# MP3_Shield.net
KiCad netlist of a schematic drawn in EAGLE
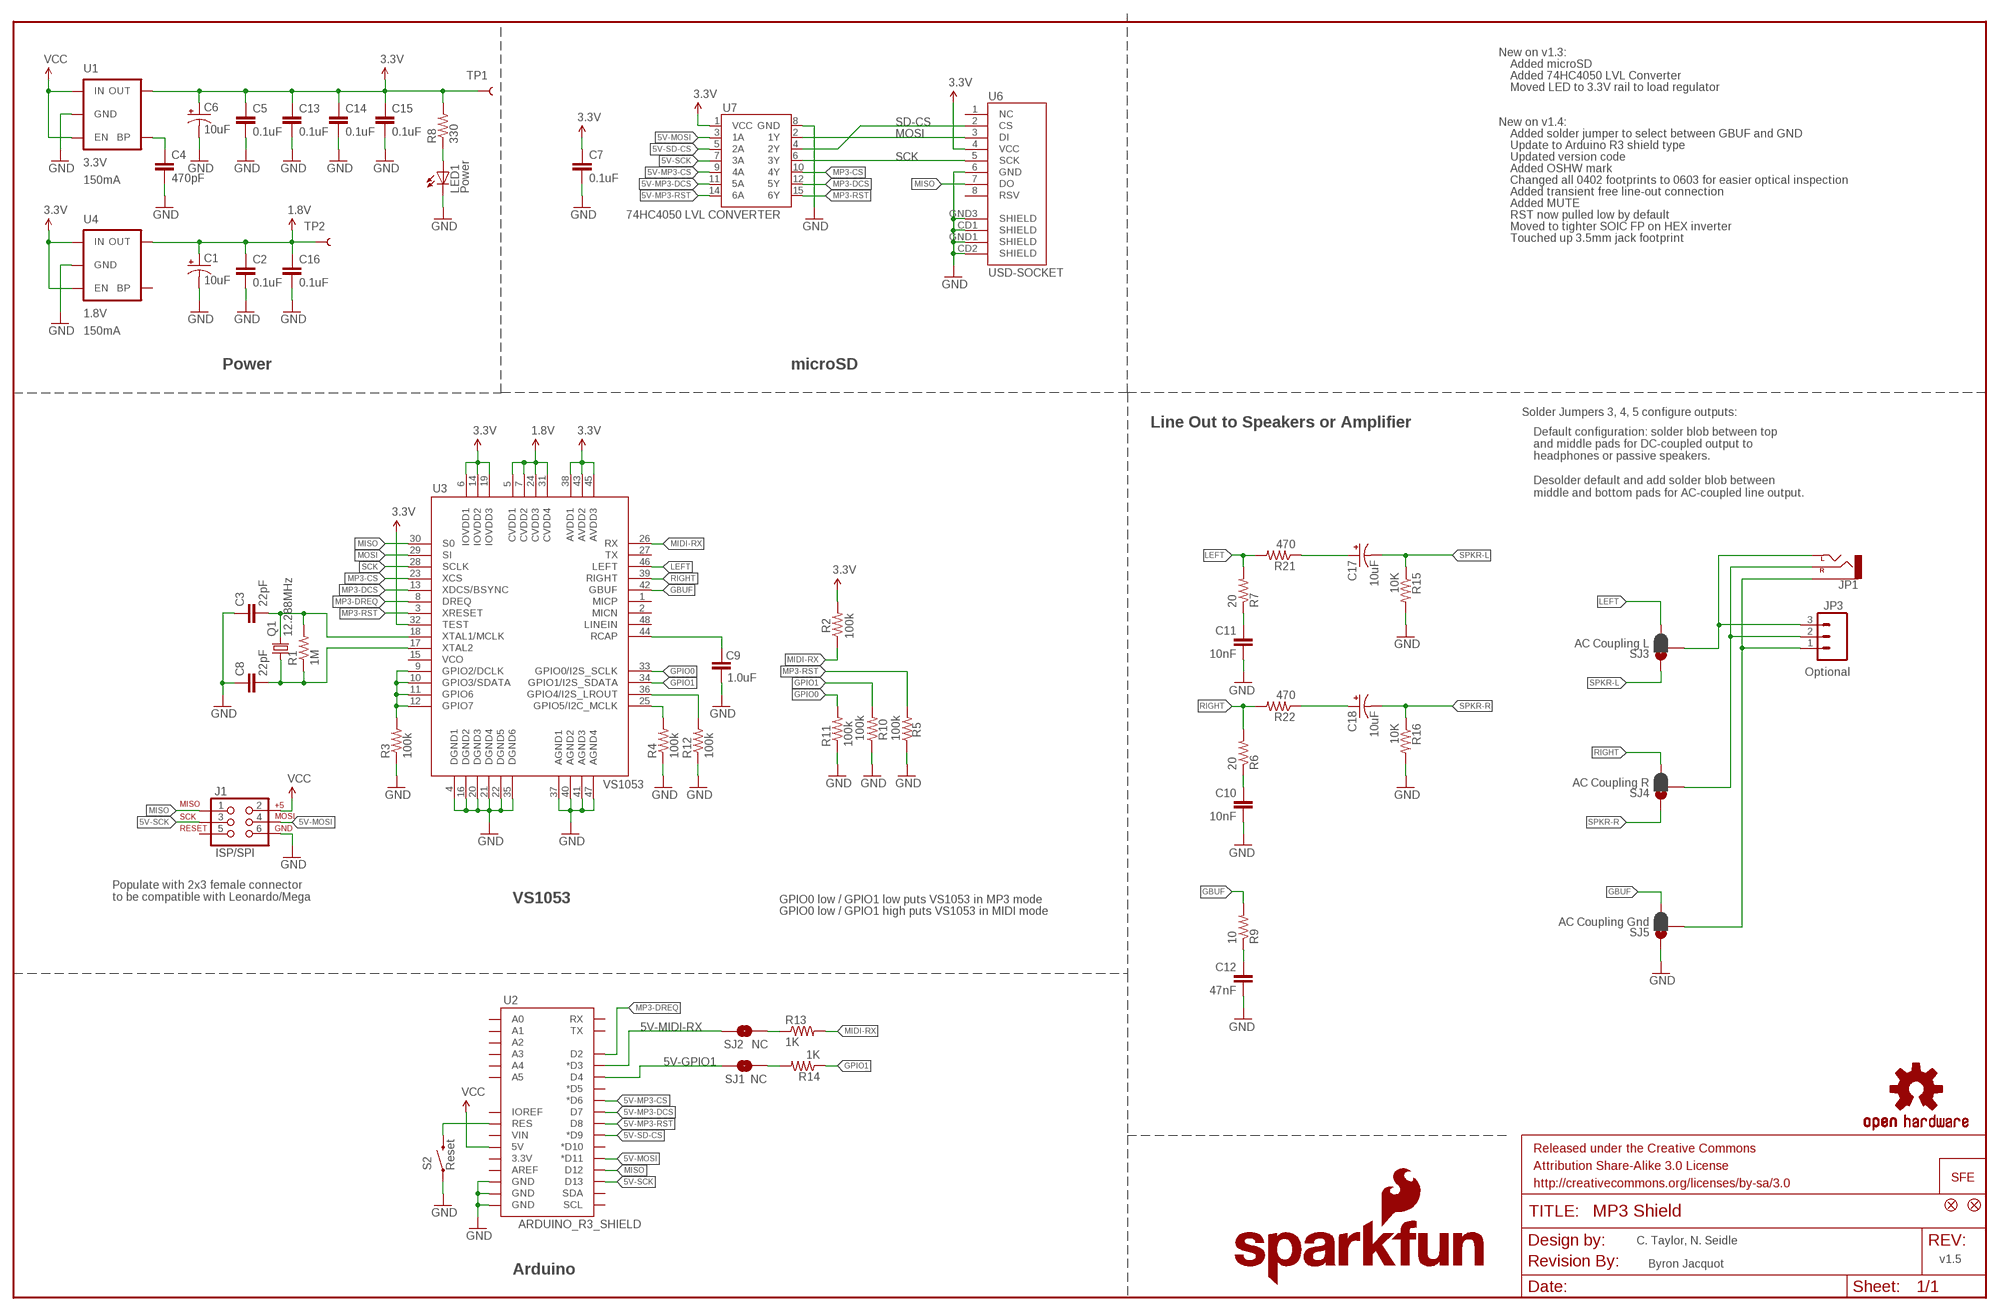
[diagram p0: schematic, sheet 1]

(export (version "E")
  (design (tool "Eeschema 10.0.6"))
  (components
    (comp (ref "C1")
      (value "10uF")
      (footprint "eagle-import:EIA3216")
      (libsource (lib "eagle-import") (part "10UF-16V-10%(TANT)"))
    )
    (comp (ref "C2")
      (value "0.1uF")
      (footprint "eagle-import:0603-CAP")
      (libsource (lib "eagle-import") (part "0.1UF-25V(+80/-20%)(0603)"))
    )
    (comp (ref "C3")
      (value "22pF")
      (footprint "eagle-import:0603-CAP")
      (libsource (lib "eagle-import") (part "22PF-50V-5%(0603)"))
    )
    (comp (ref "C4")
      (value "470pF")
      (footprint "eagle-import:0603-CAP")
      (libsource (lib "eagle-import") (part "470PF-50V-5%(0603)SMD"))
    )
    (comp (ref "C5")
      (value "0.1uF")
      (footprint "eagle-import:0603-CAP")
      (libsource (lib "eagle-import") (part "0.1UF-25V(+80/-20%)(0603)"))
    )
    (comp (ref "C6")
      (value "10uF")
      (footprint "eagle-import:EIA3216")
      (libsource (lib "eagle-import") (part "10UF-16V-10%(TANT)"))
    )
    (comp (ref "C7")
      (value "0.1uF")
      (footprint "eagle-import:0603-CAP")
      (libsource (lib "eagle-import") (part "0.1UF-25V(+80/-20%)(0603)"))
    )
    (comp (ref "C8")
      (value "22pF")
      (footprint "eagle-import:0603-CAP")
      (libsource (lib "eagle-import") (part "22PF-50V-5%(0603)"))
    )
    (comp (ref "C9")
      (value "1.0uF")
      (footprint "eagle-import:0603-CAP")
      (libsource (lib "eagle-import") (part "1.0UF-16V-10%(0603)"))
    )
    (comp (ref "C10")
      (value "10nF")
      (footprint "eagle-import:0603-CAP")
      (libsource (lib "eagle-import") (part "10NF/10000PF-50V-10%(0603)"))
    )
    (comp (ref "C11")
      (value "10nF")
      (footprint "eagle-import:0603-CAP")
      (libsource (lib "eagle-import") (part "10NF/10000PF-50V-10%(0603)"))
    )
    (comp (ref "C12")
      (value "47nF")
      (footprint "eagle-import:0603-CAP")
      (libsource (lib "eagle-import") (part "47NF(0.047UF/47000PF)-25V-5%(0603)SMD"))
    )
    (comp (ref "C13")
      (value "0.1uF")
      (footprint "eagle-import:0603-CAP")
      (libsource (lib "eagle-import") (part "0.1UF-25V(+80/-20%)(0603)"))
    )
    (comp (ref "C14")
      (value "0.1uF")
      (footprint "eagle-import:0603-CAP")
      (libsource (lib "eagle-import") (part "0.1UF-25V(+80/-20%)(0603)"))
    )
    (comp (ref "C15")
      (value "0.1uF")
      (footprint "eagle-import:0603-CAP")
      (libsource (lib "eagle-import") (part "0.1UF-25V(+80/-20%)(0603)"))
    )
    (comp (ref "C16")
      (value "0.1uF")
      (footprint "eagle-import:0603-CAP")
      (libsource (lib "eagle-import") (part "0.1UF-25V(+80/-20%)(0603)"))
    )
    (comp (ref "C17")
      (value "10uF")
      (footprint "eagle-import:EIA3216")
      (libsource (lib "eagle-import") (part "10UF-16V-10%(TANT)"))
    )
    (comp (ref "C18")
      (value "10uF")
      (footprint "eagle-import:EIA3216")
      (libsource (lib "eagle-import") (part "10UF-16V-10%(TANT)"))
    )
    (comp (ref "FRAME1")
      (value "FRAME-LEDGER")
      (footprint "eagle-import:CREATIVE_COMMONS")
      (libsource (lib "eagle-import") (part "FRAME-LEDGER"))
    )
    (comp (ref "J1")
      (value "ISP/SPI")
      (footprint "eagle-import:2X3")
      (libsource (lib "eagle-import") (part "AVR_SPI_PRG_6PTH"))
    )
    (comp (ref "JP1")
      (value "AUDIO-JACKSMD2")
      (footprint "eagle-import:AUDIO-JACK-3.5MM-SMD")
      (libsource (lib "eagle-import") (part "AUDIO-JACKSMD2"))
    )
    (comp (ref "JP3")
      (value "Optional")
      (footprint "eagle-import:1X03")
      (libsource (lib "eagle-import") (part "M03PTH"))
    )
    (comp (ref "LED1")
      (value "Power")
      (footprint "eagle-import:LED-0603")
      (libsource (lib "eagle-import") (part "LED-RED0603"))
    )
    (comp (ref "LOGO1")
      (value "OSHW-LOGOS")
      (footprint "eagle-import:OSHW-LOGO-S")
      (libsource (lib "eagle-import") (part "OSHW-LOGOS"))
    )
    (comp (ref "LOGO2")
      (value "SFE_LOGO_NAME_FLAME.1_INCH")
      (footprint "eagle-import:SFE_LOGO_NAME_FLAME_.1")
      (libsource (lib "eagle-import") (part "SFE_LOGO_NAME_FLAME.1_INCH"))
    )
    (comp (ref "Q1")
      (value "12.288MHz")
      (footprint "eagle-import:CRYSTAL-SMD-5X3")
      (libsource (lib "eagle-import") (part "CRYSTAL5X3"))
    )
    (comp (ref "R1")
      (value "1M")
      (footprint "eagle-import:0603-RES")
      (libsource (lib "eagle-import") (part "1M-1%"))
    )
    (comp (ref "R2")
      (value "100k")
      (footprint "eagle-import:0603-RES")
      (libsource (lib "eagle-import") (part "100KOHM1/10W1%(0603)"))
    )
    (comp (ref "R3")
      (value "100k")
      (footprint "eagle-import:0603-RES")
      (libsource (lib "eagle-import") (part "100KOHM1/10W1%(0603)"))
    )
    (comp (ref "R4")
      (value "100k")
      (footprint "eagle-import:0603-RES")
      (libsource (lib "eagle-import") (part "100KOHM1/10W1%(0603)"))
    )
    (comp (ref "R5")
      (value "100k")
      (footprint "eagle-import:0603-RES")
      (libsource (lib "eagle-import") (part "100KOHM1/10W1%(0603)"))
    )
    (comp (ref "R6")
      (value "20")
      (footprint "eagle-import:0603-RES")
      (libsource (lib "eagle-import") (part "20OHM1/10W1%(0603)SMD"))
    )
    (comp (ref "R7")
      (value "20")
      (footprint "eagle-import:0603-RES")
      (libsource (lib "eagle-import") (part "20OHM1/10W1%(0603)SMD"))
    )
    (comp (ref "R8")
      (value "330")
      (footprint "eagle-import:0603-RES")
      (libsource (lib "eagle-import") (part "330OHM1/10W1%(0603)"))
    )
    (comp (ref "R9")
      (value "10")
      (footprint "eagle-import:0603-RES")
      (libsource (lib "eagle-import") (part "10OHM1/10W5%0603SMD"))
    )
    (comp (ref "R10")
      (value "100k")
      (footprint "eagle-import:0603-RES")
      (libsource (lib "eagle-import") (part "100KOHM1/10W1%(0603)"))
    )
    (comp (ref "R11")
      (value "100k")
      (footprint "eagle-import:0603-RES")
      (libsource (lib "eagle-import") (part "100KOHM1/10W1%(0603)"))
    )
    (comp (ref "R12")
      (value "100k")
      (footprint "eagle-import:0603-RES")
      (libsource (lib "eagle-import") (part "100KOHM1/10W1%(0603)"))
    )
    (comp (ref "R13")
      (value "1K")
      (footprint "eagle-import:0603-RES")
      (libsource (lib "eagle-import") (part "1KOHM1/10W1%(0603)"))
    )
    (comp (ref "R14")
      (value "1K")
      (footprint "eagle-import:0603-RES")
      (libsource (lib "eagle-import") (part "1KOHM1/10W1%(0603)"))
    )
    (comp (ref "R15")
      (value "10K")
      (footprint "eagle-import:0603-RES")
      (libsource (lib "eagle-import") (part "10KOHM1/10W1%(0603)0603"))
    )
    (comp (ref "R16")
      (value "10K")
      (footprint "eagle-import:0603-RES")
      (libsource (lib "eagle-import") (part "10KOHM1/10W1%(0603)0603"))
    )
    (comp (ref "R21")
      (value "470")
      (footprint "eagle-import:0603-RES")
      (libsource (lib "eagle-import") (part "470OHM1/10W1%(0603)"))
    )
    (comp (ref "R22")
      (value "470")
      (footprint "eagle-import:0603-RES")
      (libsource (lib "eagle-import") (part "470OHM1/10W1%(0603)"))
    )
    (comp (ref "S2")
      (value "Reset")
      (footprint "eagle-import:TACTILE_SWITCH_SMD")
      (libsource (lib "eagle-import") (part "SWITCH-MOMENTARY-2SMD"))
    )
    (comp (ref "SJ1")
      (value "NC")
      (footprint "eagle-import:SJ_2S-TRACE")
      (libsource (lib "eagle-import") (part "SOLDERJUMPERTRACE"))
    )
    (comp (ref "SJ2")
      (value "NC")
      (footprint "eagle-import:SJ_2S-TRACE")
      (libsource (lib "eagle-import") (part "SOLDERJUMPERTRACE"))
    )
    (comp (ref "SJ3")
      (value "AC Coupling L")
      (footprint "eagle-import:PAD-JUMPER-3-2OF3_NC_BY_PASTE_YES_SILK_FULL_BOX")
      (libsource (lib "eagle-import") (part "JUMPER-PAD-3-2OF3_NC_BY_PASTE"))
    )
    (comp (ref "SJ4")
      (value "AC Coupling R")
      (footprint "eagle-import:PAD-JUMPER-3-2OF3_NC_BY_PASTE_YES_SILK_FULL_BOX")
      (libsource (lib "eagle-import") (part "JUMPER-PAD-3-2OF3_NC_BY_PASTE"))
    )
    (comp (ref "SJ5")
      (value "AC Coupling Gnd")
      (footprint "eagle-import:PAD-JUMPER-3-2OF3_NC_BY_PASTE_YES_SILK_FULL_BOX")
      (libsource (lib "eagle-import") (part "JUMPER-PAD-3-2OF3_NC_BY_PASTE"))
    )
    (comp (ref "TP1")
      (value "TEST-POINT3X5")
      (footprint "eagle-import:PAD.03X.05")
      (libsource (lib "eagle-import") (part "TEST-POINT3X5"))
    )
    (comp (ref "TP2")
      (value "TEST-POINT3X5")
      (footprint "eagle-import:PAD.03X.05")
      (libsource (lib "eagle-import") (part "TEST-POINT3X5"))
    )
    (comp (ref "U$1")
      (value "REVISION")
      (footprint "eagle-import:REVISION")
      (libsource (lib "eagle-import") (part "REVISION"))
    )
    (comp (ref "U$4")
      (value "FIDUCIAL1X2")
      (footprint "eagle-import:FIDUCIAL-1X2")
      (libsource (lib "eagle-import") (part "FIDUCIAL1X2"))
    )
    (comp (ref "U$5")
      (value "FIDUCIAL1X2")
      (footprint "eagle-import:FIDUCIAL-1X2")
      (libsource (lib "eagle-import") (part "FIDUCIAL1X2"))
    )
    (comp (ref "U$8")
      (value "LOGO-SFENEW")
      (footprint "eagle-import:SFE-NEW-WEBLOGO")
      (libsource (lib "eagle-import") (part "LOGO-SFENEW"))
    )
    (comp (ref "U1")
      (value "3.3V")
      (footprint "eagle-import:SOT23-5")
      (libsource (lib "eagle-import") (part "V_REG_MIC52053.3V"))
    )
    (comp (ref "U2")
      (value "ARDUINO_R3_SHIELD")
      (footprint "eagle-import:UNO_R3_SHIELD")
      (libsource (lib "eagle-import") (part "ARDUINO_R3_SHIELD"))
    )
    (comp (ref "U3")
      (value "VS1053")
      (footprint "eagle-import:LQFP-48")
      (libsource (lib "eagle-import") (part "VS1033/1053SMD"))
    )
    (comp (ref "U4")
      (value "1.8V")
      (footprint "eagle-import:SC70")
      (libsource (lib "eagle-import") (part "V_REG_SP62141.8V"))
    )
    (comp (ref "U6")
      (value "USD-SOCKET")
      (footprint "eagle-import:MICRO-SD-SOCKET-PP")
      (libsource (lib "eagle-import") (part "USD-SOCKETNEW"))
    )
    (comp (ref "U7")
      (value "74HC4050 LVL CONVERTER")
      (footprint "eagle-import:SO016")
      (libsource (lib "eagle-import") (part "HEX_CONVERTER"))
    )
  )
  (nets
    (net (code "1") (name "/5V-GPIO1") (class "Default")
      (node (ref "SJ1") (pin "2") (pinfunction "2_2") (pintype "passive"))
      (node (ref "U2") (pin "D4") (pinfunction "D4_D4") (pintype "bidirectional"))
    )
    (net (code "2") (name "/5V-MIDI-RX") (class "Default")
      (node (ref "SJ2") (pin "1") (pinfunction "1_1") (pintype "passive"))
      (node (ref "U2") (pin "D3") (pinfunction "*D3_D3") (pintype "bidirectional"))
    )
    (net (code "3") (name "/SD-CS") (class "Default")
      (node (ref "U6") (pin "2") (pinfunction "CS_2") (pintype "bidirectional"))
      (node (ref "U7") (pin "4") (pinfunction "2Y_4") (pintype "bidirectional"))
    )
    (net (code "4") (name "1.8V") (class "Default")
      (node (ref "C1") (pin "A") (pinfunction "+_A") (pintype "passive"))
      (node (ref "C16") (pin "1") (pinfunction "1_1") (pintype "passive"))
      (node (ref "C2") (pin "1") (pinfunction "1_1") (pintype "passive"))
      (node (ref "TP2") (pin "P$1") (pinfunction "1_P$1") (pintype "bidirectional"))
      (node (ref "U3") (pin "24") (pinfunction "CVDD3_24") (pintype "bidirectional"))
      (node (ref "U3") (pin "31") (pinfunction "CVDD4_31") (pintype "bidirectional"))
      (node (ref "U3") (pin "5") (pinfunction "CVDD1_5") (pintype "bidirectional"))
      (node (ref "U3") (pin "7") (pinfunction "CVDD2_7") (pintype "bidirectional"))
      (node (ref "U4") (pin "5") (pinfunction "OUT_5") (pintype "passive"))
    )
    (net (code "5") (name "3.3V") (class "Default")
      (node (ref "C13") (pin "1") (pinfunction "1_1") (pintype "passive"))
      (node (ref "C14") (pin "1") (pinfunction "1_1") (pintype "passive"))
      (node (ref "C15") (pin "1") (pinfunction "1_1") (pintype "passive"))
      (node (ref "C5") (pin "1") (pinfunction "1_1") (pintype "passive"))
      (node (ref "C6") (pin "A") (pinfunction "+_A") (pintype "passive"))
      (node (ref "C7") (pin "1") (pinfunction "1_1") (pintype "passive"))
      (node (ref "R2") (pin "2") (pinfunction "2_2") (pintype "passive"))
      (node (ref "R8") (pin "2") (pinfunction "2_2") (pintype "passive"))
      (node (ref "TP1") (pin "P$1") (pinfunction "1_P$1") (pintype "bidirectional"))
      (node (ref "U1") (pin "5") (pinfunction "OUT_5") (pintype "passive"))
      (node (ref "U3") (pin "14") (pinfunction "IOVDD2_14") (pintype "bidirectional"))
      (node (ref "U3") (pin "19") (pinfunction "IOVDD3_19") (pintype "bidirectional"))
      (node (ref "U3") (pin "32") (pinfunction "TEST_32") (pintype "bidirectional"))
      (node (ref "U3") (pin "38") (pinfunction "AVDD1_38") (pintype "bidirectional"))
      (node (ref "U3") (pin "43") (pinfunction "AVDD2_43") (pintype "bidirectional"))
      (node (ref "U3") (pin "45") (pinfunction "AVDD3_45") (pintype "bidirectional"))
      (node (ref "U3") (pin "6") (pinfunction "IOVDD1_6") (pintype "bidirectional"))
      (node (ref "U4") (pin "1") (pinfunction "IN_1") (pintype "input"))
      (node (ref "U4") (pin "3") (pinfunction "EN_3") (pintype "input"))
      (node (ref "U6") (pin "4") (pinfunction "VCC_4") (pintype "bidirectional"))
      (node (ref "U7") (pin "1") (pinfunction "VCC_1") (pintype "bidirectional"))
    )
    (net (code "6") (name "5V-MOSI") (class "Default")
      (node (ref "J1") (pin "4") (pinfunction "4_4") (pintype "passive"))
      (node (ref "U2") (pin "D11") (pinfunction "*D11_D11") (pintype "bidirectional"))
      (node (ref "U7") (pin "3") (pinfunction "1A_3") (pintype "bidirectional"))
    )
    (net (code "7") (name "5V-MP3-CS") (class "Default")
      (node (ref "U2") (pin "D6") (pinfunction "*D6_D6") (pintype "bidirectional"))
      (node (ref "U7") (pin "9") (pinfunction "4A_9") (pintype "bidirectional"))
    )
    (net (code "8") (name "5V-MP3-DCS") (class "Default")
      (node (ref "U2") (pin "D7") (pinfunction "D7_D7") (pintype "bidirectional"))
      (node (ref "U7") (pin "11") (pinfunction "5A_11") (pintype "bidirectional"))
    )
    (net (code "9") (name "5V-MP3-RST") (class "Default")
      (node (ref "U2") (pin "D8") (pinfunction "D8_D8") (pintype "bidirectional"))
      (node (ref "U7") (pin "14") (pinfunction "6A_14") (pintype "bidirectional"))
    )
    (net (code "10") (name "5V-SCK") (class "Default")
      (node (ref "J1") (pin "3") (pinfunction "3_3") (pintype "passive"))
      (node (ref "U2") (pin "D13") (pinfunction "D13_D13") (pintype "bidirectional"))
      (node (ref "U7") (pin "7") (pinfunction "3A_7") (pintype "bidirectional"))
    )
    (net (code "11") (name "5V-SD-CS") (class "Default")
      (node (ref "U2") (pin "D9") (pinfunction "*D9_D9") (pintype "bidirectional"))
      (node (ref "U7") (pin "5") (pinfunction "2A_5") (pintype "bidirectional"))
    )
    (net (code "12") (name "GBUF") (class "Default")
      (node (ref "R9") (pin "2") (pinfunction "2_2") (pintype "passive"))
      (node (ref "SJ5") (pin "3") (pinfunction "3_3") (pintype "passive"))
      (node (ref "U3") (pin "42") (pinfunction "GBUF_42") (pintype "bidirectional"))
    )
    (net (code "13") (name "GND") (class "Default")
      (node (ref "C1") (pin "C") (pinfunction "-_C") (pintype "passive"))
      (node (ref "C10") (pin "2") (pinfunction "2_2") (pintype "passive"))
      (node (ref "C11") (pin "2") (pinfunction "2_2") (pintype "passive"))
      (node (ref "C12") (pin "2") (pinfunction "2_2") (pintype "passive"))
      (node (ref "C13") (pin "2") (pinfunction "2_2") (pintype "passive"))
      (node (ref "C14") (pin "2") (pinfunction "2_2") (pintype "passive"))
      (node (ref "C15") (pin "2") (pinfunction "2_2") (pintype "passive"))
      (node (ref "C16") (pin "2") (pinfunction "2_2") (pintype "passive"))
      (node (ref "C2") (pin "2") (pinfunction "2_2") (pintype "passive"))
      (node (ref "C3") (pin "1") (pinfunction "1_1") (pintype "passive"))
      (node (ref "C4") (pin "2") (pinfunction "2_2") (pintype "passive"))
      (node (ref "C5") (pin "2") (pinfunction "2_2") (pintype "passive"))
      (node (ref "C6") (pin "C") (pinfunction "-_C") (pintype "passive"))
      (node (ref "C7") (pin "2") (pinfunction "2_2") (pintype "passive"))
      (node (ref "C8") (pin "1") (pinfunction "1_1") (pintype "passive"))
      (node (ref "C9") (pin "1") (pinfunction "1_1") (pintype "passive"))
      (node (ref "J1") (pin "6") (pinfunction "6_6") (pintype "passive"))
      (node (ref "LED1") (pin "C") (pinfunction "C_C") (pintype "passive"))
      (node (ref "R10") (pin "1") (pinfunction "1_1") (pintype "passive"))
      (node (ref "R11") (pin "1") (pinfunction "1_1") (pintype "passive"))
      (node (ref "R12") (pin "1") (pinfunction "1_1") (pintype "passive"))
      (node (ref "R15") (pin "2") (pinfunction "2_2") (pintype "passive"))
      (node (ref "R16") (pin "2") (pinfunction "2_2") (pintype "passive"))
      (node (ref "R3") (pin "1") (pinfunction "1_1") (pintype "passive"))
      (node (ref "R4") (pin "1") (pinfunction "1_1") (pintype "passive"))
      (node (ref "R5") (pin "1") (pinfunction "1_1") (pintype "passive"))
      (node (ref "S2") (pin "1") (pinfunction "1_1") (pintype "passive"))
      (node (ref "SJ5") (pin "1") (pinfunction "1_1") (pintype "passive"))
      (node (ref "U1") (pin "2") (pinfunction "GND_2") (pintype "input"))
      (node (ref "U2") (pin "GND@0") (pinfunction "GND_GND@0") (pintype "bidirectional"))
      (node (ref "U2") (pin "GND@1") (pinfunction "GND_GND@1") (pintype "bidirectional"))
      (node (ref "U2") (pin "GND@2") (pinfunction "GND_GND@2") (pintype "bidirectional"))
      (node (ref "U3") (pin "16") (pinfunction "DGND2_16") (pintype "bidirectional"))
      (node (ref "U3") (pin "20") (pinfunction "DGND3_20") (pintype "bidirectional"))
      (node (ref "U3") (pin "21") (pinfunction "DGND4_21") (pintype "bidirectional"))
      (node (ref "U3") (pin "22") (pinfunction "DGND5_22") (pintype "bidirectional"))
      (node (ref "U3") (pin "35") (pinfunction "DGND6_35") (pintype "bidirectional"))
      (node (ref "U3") (pin "37") (pinfunction "AGND1_37") (pintype "bidirectional"))
      (node (ref "U3") (pin "4") (pinfunction "DGND1_4") (pintype "bidirectional"))
      (node (ref "U3") (pin "40") (pinfunction "AGND2_40") (pintype "bidirectional"))
      (node (ref "U3") (pin "41") (pinfunction "AGND3_41") (pintype "bidirectional"))
      (node (ref "U3") (pin "47") (pinfunction "AGND4_47") (pintype "bidirectional"))
      (node (ref "U4") (pin "2") (pinfunction "GND_2") (pintype "input"))
      (node (ref "U6") (pin "6") (pinfunction "GND_6") (pintype "bidirectional"))
      (node (ref "U6") (pin "CD1") (pinfunction "SHIELD_CD1") (pintype "bidirectional"))
      (node (ref "U6") (pin "CD2") (pinfunction "SHIELD_CD2") (pintype "bidirectional"))
      (node (ref "U6") (pin "GND1") (pinfunction "SHIELD_GND1") (pintype "bidirectional"))
      (node (ref "U6") (pin "GND3") (pinfunction "SHIELD_GND3") (pintype "bidirectional"))
      (node (ref "U7") (pin "8") (pinfunction "GND_8") (pintype "bidirectional"))
    )
    (net (code "14") (name "GPIO0") (class "Default")
      (node (ref "R11") (pin "2") (pinfunction "2_2") (pintype "passive"))
      (node (ref "U3") (pin "33") (pinfunction "GPIO0/I2S_SCLK_33") (pintype "bidirectional"))
    )
    (net (code "15") (name "GPIO1") (class "Default")
      (node (ref "R10") (pin "2") (pinfunction "2_2") (pintype "passive"))
      (node (ref "R14") (pin "1") (pinfunction "1_1") (pintype "passive"))
      (node (ref "U3") (pin "34") (pinfunction "GPIO1/I2S_SDATA_34") (pintype "bidirectional"))
    )
    (net (code "16") (name "LEFT") (class "Default")
      (node (ref "R21") (pin "2") (pinfunction "2_2") (pintype "passive"))
      (node (ref "R7") (pin "2") (pinfunction "2_2") (pintype "passive"))
      (node (ref "SJ3") (pin "3") (pinfunction "3_3") (pintype "passive"))
      (node (ref "U3") (pin "46") (pinfunction "LEFT_46") (pintype "bidirectional"))
    )
    (net (code "17") (name "MIDI-RX") (class "Default")
      (node (ref "R13") (pin "2") (pinfunction "2_2") (pintype "passive"))
      (node (ref "R2") (pin "1") (pinfunction "1_1") (pintype "passive"))
      (node (ref "U3") (pin "26") (pinfunction "RX_26") (pintype "bidirectional"))
    )
    (net (code "18") (name "MISO") (class "Default")
      (node (ref "J1") (pin "1") (pinfunction "1_1") (pintype "passive"))
      (node (ref "U2") (pin "D12") (pinfunction "D12_D12") (pintype "bidirectional"))
      (node (ref "U3") (pin "30") (pinfunction "S0_30") (pintype "bidirectional"))
      (node (ref "U6") (pin "7") (pinfunction "DO_7") (pintype "bidirectional"))
    )
    (net (code "19") (name "MOSI") (class "Default")
      (node (ref "U3") (pin "29") (pinfunction "SI_29") (pintype "bidirectional"))
      (node (ref "U6") (pin "3") (pinfunction "DI_3") (pintype "bidirectional"))
      (node (ref "U7") (pin "2") (pinfunction "1Y_2") (pintype "bidirectional"))
    )
    (net (code "20") (name "MP3-CS") (class "Default")
      (node (ref "U3") (pin "23") (pinfunction "XCS_23") (pintype "bidirectional"))
      (node (ref "U7") (pin "10") (pinfunction "4Y_10") (pintype "bidirectional"))
    )
    (net (code "21") (name "MP3-DCS") (class "Default")
      (node (ref "U3") (pin "13") (pinfunction "XDCS/BSYNC_13") (pintype "bidirectional"))
      (node (ref "U7") (pin "12") (pinfunction "5Y_12") (pintype "bidirectional"))
    )
    (net (code "22") (name "MP3-DREQ") (class "Default")
      (node (ref "U2") (pin "D2") (pinfunction "D2_D2") (pintype "bidirectional"))
      (node (ref "U3") (pin "8") (pinfunction "DREQ_8") (pintype "bidirectional"))
    )
    (net (code "23") (name "MP3-RST") (class "Default")
      (node (ref "R5") (pin "2") (pinfunction "2_2") (pintype "passive"))
      (node (ref "U3") (pin "3") (pinfunction "XRESET_3") (pintype "bidirectional"))
      (node (ref "U7") (pin "15") (pinfunction "6Y_15") (pintype "bidirectional"))
    )
    (net (code "24") (name "Net-(C10-Pad1)") (class "Default")
      (node (ref "C10") (pin "1") (pinfunction "1_1") (pintype "passive"))
      (node (ref "R6") (pin "1") (pinfunction "1_1") (pintype "passive"))
    )
    (net (code "25") (name "Net-(C11-Pad1)") (class "Default")
      (node (ref "C11") (pin "1") (pinfunction "1_1") (pintype "passive"))
      (node (ref "R7") (pin "1") (pinfunction "1_1") (pintype "passive"))
    )
    (net (code "26") (name "Net-(C12-Pad1)") (class "Default")
      (node (ref "C12") (pin "1") (pinfunction "1_1") (pintype "passive"))
      (node (ref "R9") (pin "1") (pinfunction "1_1") (pintype "passive"))
    )
    (net (code "27") (name "Net-(C17-+)") (class "Default")
      (node (ref "C17") (pin "A") (pinfunction "+_A") (pintype "passive"))
      (node (ref "R21") (pin "1") (pinfunction "1_1") (pintype "passive"))
    )
    (net (code "28") (name "Net-(C18-+)") (class "Default")
      (node (ref "C18") (pin "A") (pinfunction "+_A") (pintype "passive"))
      (node (ref "R22") (pin "1") (pinfunction "1_1") (pintype "passive"))
    )
    (net (code "29") (name "Net-(JP1-LEFT)") (class "Default")
      (node (ref "JP1") (pin "TIP") (pinfunction "LEFT_TIP") (pintype "bidirectional"))
      (node (ref "JP3") (pin "3") (pinfunction "3_3") (pintype "passive"))
      (node (ref "SJ3") (pin "2") (pinfunction "2_2") (pintype "passive"))
    )
    (net (code "30") (name "Net-(JP1-PadSLEEVE)") (class "Default")
      (node (ref "JP1") (pin "SLEEVE") (pinfunction "SLEEVE_SLEEVE") (pintype "bidirectional"))
      (node (ref "JP3") (pin "1") (pinfunction "1_1") (pintype "passive"))
      (node (ref "SJ5") (pin "2") (pinfunction "2_2") (pintype "passive"))
    )
    (net (code "31") (name "Net-(JP1-RIGHT)") (class "Default")
      (node (ref "JP1") (pin "RING") (pinfunction "RIGHT_RING") (pintype "bidirectional"))
      (node (ref "JP3") (pin "2") (pinfunction "2_2") (pintype "passive"))
      (node (ref "SJ4") (pin "2") (pinfunction "2_2") (pintype "passive"))
    )
    (net (code "32") (name "Net-(LED1-PadA)") (class "Default")
      (node (ref "LED1") (pin "A") (pinfunction "A_A") (pintype "passive"))
      (node (ref "R8") (pin "1") (pinfunction "1_1") (pintype "passive"))
    )
    (net (code "33") (name "Net-(Q1-2)") (class "Default")
      (node (ref "C3") (pin "2") (pinfunction "2_2") (pintype "passive"))
      (node (ref "Q1") (pin "3") (pinfunction "2_3") (pintype "passive"))
      (node (ref "R1") (pin "2") (pinfunction "2_2") (pintype "passive"))
      (node (ref "U3") (pin "18") (pinfunction "XTAL1/MCLK_18") (pintype "bidirectional"))
    )
    (net (code "34") (name "Net-(R13-Pad1)") (class "Default")
      (node (ref "R13") (pin "1") (pinfunction "1_1") (pintype "passive"))
      (node (ref "SJ2") (pin "2") (pinfunction "2_2") (pintype "passive"))
    )
    (net (code "35") (name "Net-(R14-Pad2)") (class "Default")
      (node (ref "R14") (pin "2") (pinfunction "2_2") (pintype "passive"))
      (node (ref "SJ1") (pin "1") (pinfunction "1_1") (pintype "passive"))
    )
    (net (code "36") (name "Net-(S2-2)") (class "Default")
      (node (ref "S2") (pin "3") (pinfunction "2_3") (pintype "passive"))
      (node (ref "U2") (pin "RES") (pinfunction "RES_RES") (pintype "bidirectional"))
    )
    (net (code "37") (name "Net-(U1-BP)") (class "Default")
      (node (ref "C4") (pin "1") (pinfunction "1_1") (pintype "passive"))
      (node (ref "U1") (pin "4") (pinfunction "BP_4") (pintype "input"))
    )
    (net (code "38") (name "Net-(U3-GPIO2{slash}DCLK)") (class "Default")
      (node (ref "R3") (pin "2") (pinfunction "2_2") (pintype "passive"))
      (node (ref "U3") (pin "10") (pinfunction "GPIO3/SDATA_10") (pintype "bidirectional"))
      (node (ref "U3") (pin "11") (pinfunction "GPIO6_11") (pintype "bidirectional"))
      (node (ref "U3") (pin "12") (pinfunction "GPIO7_12") (pintype "bidirectional"))
      (node (ref "U3") (pin "9") (pinfunction "GPIO2/DCLK_9") (pintype "bidirectional"))
    )
    (net (code "39") (name "Net-(U3-GPIO4{slash}I2S_LROUT)") (class "Default")
      (node (ref "R12") (pin "2") (pinfunction "2_2") (pintype "passive"))
      (node (ref "U3") (pin "36") (pinfunction "GPIO4/I2S_LROUT_36") (pintype "bidirectional"))
    )
    (net (code "40") (name "Net-(U3-GPIO5{slash}I2C_MCLK)") (class "Default")
      (node (ref "R4") (pin "2") (pinfunction "2_2") (pintype "passive"))
      (node (ref "U3") (pin "25") (pinfunction "GPIO5/I2C_MCLK_25") (pintype "bidirectional"))
    )
    (net (code "41") (name "Net-(U3-RCAP)") (class "Default")
      (node (ref "C9") (pin "2") (pinfunction "2_2") (pintype "passive"))
      (node (ref "U3") (pin "44") (pinfunction "RCAP_44") (pintype "bidirectional"))
    )
    (net (code "42") (name "Net-(U3-XTAL2)") (class "Default")
      (node (ref "C8") (pin "2") (pinfunction "2_2") (pintype "passive"))
      (node (ref "Q1") (pin "1") (pinfunction "1_1") (pintype "passive"))
      (node (ref "R1") (pin "1") (pinfunction "1_1") (pintype "passive"))
      (node (ref "U3") (pin "17") (pinfunction "XTAL2_17") (pintype "bidirectional"))
    )
    (net (code "43") (name "RIGHT") (class "Default")
      (node (ref "R22") (pin "2") (pinfunction "2_2") (pintype "passive"))
      (node (ref "R6") (pin "2") (pinfunction "2_2") (pintype "passive"))
      (node (ref "SJ4") (pin "3") (pinfunction "3_3") (pintype "passive"))
      (node (ref "U3") (pin "39") (pinfunction "RIGHT_39") (pintype "bidirectional"))
    )
    (net (code "44") (name "SCK") (class "Default")
      (node (ref "U3") (pin "28") (pinfunction "SCLK_28") (pintype "bidirectional"))
      (node (ref "U6") (pin "5") (pinfunction "SCK_5") (pintype "bidirectional"))
      (node (ref "U7") (pin "6") (pinfunction "3Y_6") (pintype "bidirectional"))
    )
    (net (code "45") (name "SPKR-L") (class "Default")
      (node (ref "C17") (pin "C") (pinfunction "-_C") (pintype "passive"))
      (node (ref "R15") (pin "1") (pinfunction "1_1") (pintype "passive"))
      (node (ref "SJ3") (pin "1") (pinfunction "1_1") (pintype "passive"))
    )
    (net (code "46") (name "SPKR-R") (class "Default")
      (node (ref "C18") (pin "C") (pinfunction "-_C") (pintype "passive"))
      (node (ref "R16") (pin "1") (pinfunction "1_1") (pintype "passive"))
      (node (ref "SJ4") (pin "1") (pinfunction "1_1") (pintype "passive"))
    )
    (net (code "47") (name "VCC") (class "Default")
      (node (ref "J1") (pin "2") (pinfunction "2_2") (pintype "passive"))
      (node (ref "U1") (pin "1") (pinfunction "IN_1") (pintype "input"))
      (node (ref "U1") (pin "3") (pinfunction "EN_3") (pintype "input"))
      (node (ref "U2") (pin "5V") (pinfunction "5V_5V") (pintype "bidirectional"))
    )
    (net (code "48") (name "unconnected-(J1-Pad5)") (class "Default")
      (node (ref "J1") (pin "5") (pinfunction "5_5") (pintype "passive"))
    )
    (net (code "49") (name "unconnected-(U2-*D5-PadD5)") (class "Default")
      (node (ref "U2") (pin "D5") (pinfunction "*D5_D5") (pintype "bidirectional"))
    )
    (net (code "50") (name "unconnected-(U2-*D10-PadD10)") (class "Default")
      (node (ref "U2") (pin "D10") (pinfunction "*D10_D10") (pintype "bidirectional"))
    )
    (net (code "51") (name "unconnected-(U2-Pad3.3V)") (class "Default")
      (node (ref "U2") (pin "3.3V") (pinfunction "3.3V_3.3V") (pintype "bidirectional"))
    )
    (net (code "52") (name "unconnected-(U2-PadA0)") (class "Default")
      (node (ref "U2") (pin "A0") (pinfunction "A0_A0") (pintype "bidirectional"))
    )
    (net (code "53") (name "unconnected-(U2-PadA1)") (class "Default")
      (node (ref "U2") (pin "A1") (pinfunction "A1_A1") (pintype "bidirectional"))
    )
    (net (code "54") (name "unconnected-(U2-PadA2)") (class "Default")
      (node (ref "U2") (pin "A2") (pinfunction "A2_A2") (pintype "bidirectional"))
    )
    (net (code "55") (name "unconnected-(U2-PadA3)") (class "Default")
      (node (ref "U2") (pin "A3") (pinfunction "A3_A3") (pintype "bidirectional"))
    )
    (net (code "56") (name "unconnected-(U2-PadA4)") (class "Default")
      (node (ref "U2") (pin "A4") (pinfunction "A4_A4") (pintype "bidirectional"))
    )
    (net (code "57") (name "unconnected-(U2-PadA5)") (class "Default")
      (node (ref "U2") (pin "A5") (pinfunction "A5_A5") (pintype "bidirectional"))
    )
    (net (code "58") (name "unconnected-(U2-PadAREF)") (class "Default")
      (node (ref "U2") (pin "AREF") (pinfunction "AREF_AREF") (pintype "bidirectional"))
    )
    (net (code "59") (name "unconnected-(U2-PadIOREF)") (class "Default")
      (node (ref "U2") (pin "IOREF") (pinfunction "IOREF_IOREF") (pintype "bidirectional"))
    )
    (net (code "60") (name "unconnected-(U2-PadRX)") (class "Default")
      (node (ref "U2") (pin "RX") (pinfunction "RX_RX") (pintype "bidirectional"))
    )
    (net (code "61") (name "unconnected-(U2-PadSCL)") (class "Default")
      (node (ref "U2") (pin "SCL") (pinfunction "SCL_SCL") (pintype "bidirectional"))
    )
    (net (code "62") (name "unconnected-(U2-PadSDA)") (class "Default")
      (node (ref "U2") (pin "SDA") (pinfunction "SDA_SDA") (pintype "bidirectional"))
    )
    (net (code "63") (name "unconnected-(U2-PadTX)") (class "Default")
      (node (ref "U2") (pin "TX") (pinfunction "TX_TX") (pintype "bidirectional"))
    )
    (net (code "64") (name "unconnected-(U2-PadVIN)") (class "Default")
      (node (ref "U2") (pin "VIN") (pinfunction "VIN_VIN") (pintype "bidirectional"))
    )
    (net (code "65") (name "unconnected-(U3-LINEIN-Pad48)") (class "Default")
      (node (ref "U3") (pin "48") (pinfunction "LINEIN_48") (pintype "bidirectional"))
    )
    (net (code "66") (name "unconnected-(U3-MICN-Pad2)") (class "Default")
      (node (ref "U3") (pin "2") (pinfunction "MICN_2") (pintype "bidirectional"))
    )
    (net (code "67") (name "unconnected-(U3-MICP-Pad1)") (class "Default")
      (node (ref "U3") (pin "1") (pinfunction "MICP_1") (pintype "bidirectional"))
    )
    (net (code "68") (name "unconnected-(U3-TX-Pad27)") (class "Default")
      (node (ref "U3") (pin "27") (pinfunction "TX_27") (pintype "bidirectional"))
    )
    (net (code "69") (name "unconnected-(U3-VCO-Pad15)") (class "Default")
      (node (ref "U3") (pin "15") (pinfunction "VCO_15") (pintype "bidirectional"))
    )
    (net (code "70") (name "unconnected-(U4-BP-Pad4)") (class "Default")
      (node (ref "U4") (pin "4") (pinfunction "BP_4") (pintype "input"))
    )
    (net (code "71") (name "unconnected-(U6-NC-Pad1)") (class "Default")
      (node (ref "U6") (pin "1") (pinfunction "NC_1") (pintype "bidirectional"))
    )
    (net (code "72") (name "unconnected-(U6-RSV-Pad8)") (class "Default")
      (node (ref "U6") (pin "8") (pinfunction "RSV_8") (pintype "bidirectional"))
    )
  )
)
